# BartendingRobotPCB.net
KiCad netlist of a schematic drawn in EAGLE
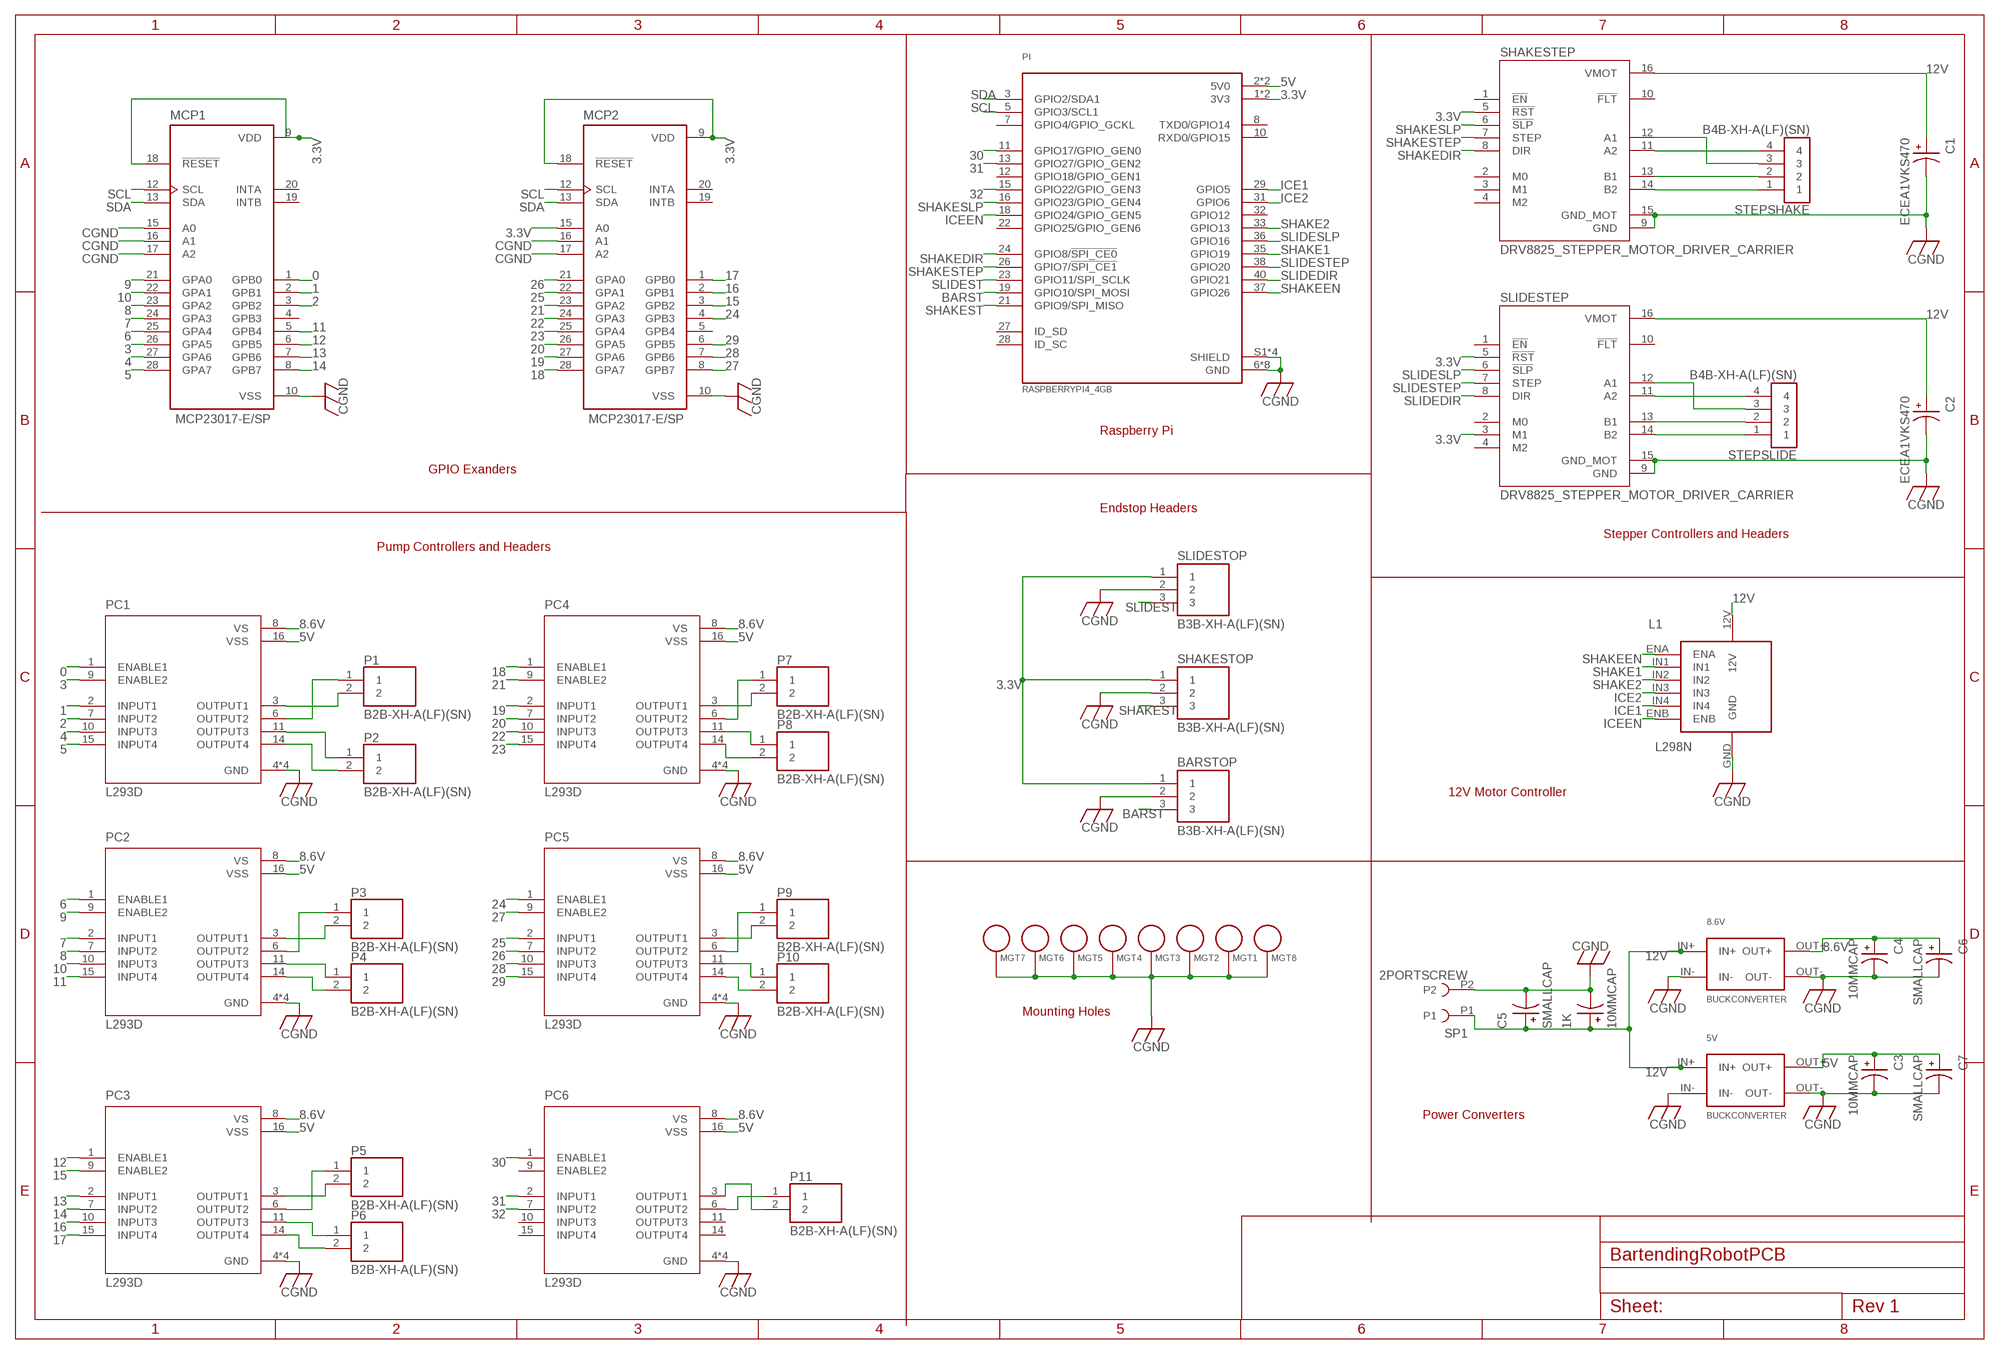
[diagram p0: schematic, sheet 1]

(export (version "E")
  (design (tool "Eeschema 10.0.6"))
  (components
    (comp (ref "1K")
      (value "10MMCAP")
      (footprint "eagle-import:10MMCAP")
      (libsource (lib "eagle-import") (part "10MMCAP"))
    )
    (comp (ref "5V")
      (value "BUCKCONVERTER")
      (footprint "eagle-import:BUCKCONVERTER")
      (libsource (lib "eagle-import") (part "BUCKCONVERTER"))
    )
    (comp (ref "8.6V")
      (value "BUCKCONVERTER")
      (footprint "eagle-import:BUCKCONVERTER")
      (libsource (lib "eagle-import") (part "BUCKCONVERTER"))
    )
    (comp (ref "BARSTOP")
      (value "B3B-XH-A(LF)(SN)")
      (footprint "eagle-import:JST_B3B-XH-A(LF)(SN)")
      (fields (field (name "MF") "JST Sales"))
      (libsource (lib "eagle-import") (part "B3B-XH-A(LF)(SN)"))
    )
    (comp (ref "C1")
      (value "ECEA1VKS470")
      (footprint "eagle-import:CAPPRD250W45D800H500")
      (fields (field (name "MF") "PANASONIC"))
      (libsource (lib "eagle-import") (part "ECEA1VKS470"))
    )
    (comp (ref "C2")
      (value "ECEA1VKS470")
      (footprint "eagle-import:CAPPRD250W45D800H500")
      (fields (field (name "MF") "PANASONIC"))
      (libsource (lib "eagle-import") (part "ECEA1VKS470"))
    )
    (comp (ref "C3")
      (value "10MMCAP")
      (footprint "eagle-import:10MMCAP")
      (libsource (lib "eagle-import") (part "10MMCAP"))
    )
    (comp (ref "C4")
      (value "10MMCAP")
      (footprint "eagle-import:10MMCAP")
      (libsource (lib "eagle-import") (part "10MMCAP"))
    )
    (comp (ref "C5")
      (value "SMALLCAP")
      (footprint "eagle-import:SMALLCAP")
      (libsource (lib "eagle-import") (part "SMALLCAP"))
    )
    (comp (ref "C6")
      (value "SMALLCAP")
      (footprint "eagle-import:SMALLCAP")
      (libsource (lib "eagle-import") (part "SMALLCAP"))
    )
    (comp (ref "C7")
      (value "SMALLCAP")
      (footprint "eagle-import:SMALLCAP")
      (libsource (lib "eagle-import") (part "SMALLCAP"))
    )
    (comp (ref "L1")
      (value "L298N")
      (footprint "eagle-import:L298N")
      (libsource (lib "eagle-import") (part "L298N"))
    )
    (comp (ref "MCP1")
      (value "MCP23017-E/SP")
      (footprint "eagle-import:DIP787W45P254L3556H508Q28")
      (fields (field (name "MF") "Microchip"))
      (libsource (lib "eagle-import") (part "MCP23017-E/SP"))
    )
    (comp (ref "MCP2")
      (value "MCP23017-E/SP")
      (footprint "eagle-import:DIP787W45P254L3556H508Q28")
      (fields (field (name "MF") "Microchip"))
      (libsource (lib "eagle-import") (part "MCP23017-E/SP"))
    )
    (comp (ref "MGT1")
      (value "MOUNTING_HOLE")
      (footprint "eagle-import:MOUNTING_HOLE")
      (libsource (lib "eagle-import") (part "MOUNTING_HOLE"))
    )
    (comp (ref "MGT2")
      (value "MOUNTING_HOLE")
      (footprint "eagle-import:MOUNTING_HOLE")
      (libsource (lib "eagle-import") (part "MOUNTING_HOLE"))
    )
    (comp (ref "MGT3")
      (value "MOUNTING_HOLE")
      (footprint "eagle-import:MOUNTING_HOLE")
      (libsource (lib "eagle-import") (part "MOUNTING_HOLE"))
    )
    (comp (ref "MGT4")
      (value "MOUNTING_HOLE")
      (footprint "eagle-import:MOUNTING_HOLE")
      (libsource (lib "eagle-import") (part "MOUNTING_HOLE"))
    )
    (comp (ref "MGT5")
      (value "MOUNTING_HOLE")
      (footprint "eagle-import:MOUNTING_HOLE")
      (libsource (lib "eagle-import") (part "MOUNTING_HOLE"))
    )
    (comp (ref "MGT6")
      (value "MOUNTING_HOLE")
      (footprint "eagle-import:MOUNTING_HOLE")
      (libsource (lib "eagle-import") (part "MOUNTING_HOLE"))
    )
    (comp (ref "MGT7")
      (value "MOUNTING_HOLE")
      (footprint "eagle-import:MOUNTING_HOLE")
      (libsource (lib "eagle-import") (part "MOUNTING_HOLE"))
    )
    (comp (ref "MGT8")
      (value "MOUNTING_HOLE")
      (footprint "eagle-import:MOUNTING_HOLE")
      (libsource (lib "eagle-import") (part "MOUNTING_HOLE"))
    )
    (comp (ref "P1")
      (value "B2B-XH-A(LF)(SN)")
      (footprint "eagle-import:JST_B2B-XH-A(LF)(SN)")
      (fields (field (name "MF") "JST Sales"))
      (libsource (lib "eagle-import") (part "B2B-XH-A(LF)(SN)"))
    )
    (comp (ref "P2")
      (value "B2B-XH-A(LF)(SN)")
      (footprint "eagle-import:JST_B2B-XH-A(LF)(SN)")
      (fields (field (name "MF") "JST Sales"))
      (libsource (lib "eagle-import") (part "B2B-XH-A(LF)(SN)"))
    )
    (comp (ref "P3")
      (value "B2B-XH-A(LF)(SN)")
      (footprint "eagle-import:JST_B2B-XH-A(LF)(SN)")
      (fields (field (name "MF") "JST Sales"))
      (libsource (lib "eagle-import") (part "B2B-XH-A(LF)(SN)"))
    )
    (comp (ref "P4")
      (value "B2B-XH-A(LF)(SN)")
      (footprint "eagle-import:JST_B2B-XH-A(LF)(SN)")
      (fields (field (name "MF") "JST Sales"))
      (libsource (lib "eagle-import") (part "B2B-XH-A(LF)(SN)"))
    )
    (comp (ref "P5")
      (value "B2B-XH-A(LF)(SN)")
      (footprint "eagle-import:JST_B2B-XH-A(LF)(SN)")
      (fields (field (name "MF") "JST Sales"))
      (libsource (lib "eagle-import") (part "B2B-XH-A(LF)(SN)"))
    )
    (comp (ref "P6")
      (value "B2B-XH-A(LF)(SN)")
      (footprint "eagle-import:JST_B2B-XH-A(LF)(SN)")
      (fields (field (name "MF") "JST Sales"))
      (libsource (lib "eagle-import") (part "B2B-XH-A(LF)(SN)"))
    )
    (comp (ref "P7")
      (value "B2B-XH-A(LF)(SN)")
      (footprint "eagle-import:JST_B2B-XH-A(LF)(SN)")
      (fields (field (name "MF") "JST Sales"))
      (libsource (lib "eagle-import") (part "B2B-XH-A(LF)(SN)"))
    )
    (comp (ref "P8")
      (value "B2B-XH-A(LF)(SN)")
      (footprint "eagle-import:JST_B2B-XH-A(LF)(SN)")
      (fields (field (name "MF") "JST Sales"))
      (libsource (lib "eagle-import") (part "B2B-XH-A(LF)(SN)"))
    )
    (comp (ref "P9")
      (value "B2B-XH-A(LF)(SN)")
      (footprint "eagle-import:JST_B2B-XH-A(LF)(SN)")
      (fields (field (name "MF") "JST Sales"))
      (libsource (lib "eagle-import") (part "B2B-XH-A(LF)(SN)"))
    )
    (comp (ref "P10")
      (value "B2B-XH-A(LF)(SN)")
      (footprint "eagle-import:JST_B2B-XH-A(LF)(SN)")
      (fields (field (name "MF") "JST Sales"))
      (libsource (lib "eagle-import") (part "B2B-XH-A(LF)(SN)"))
    )
    (comp (ref "P11")
      (value "B2B-XH-A(LF)(SN)")
      (footprint "eagle-import:JST_B2B-XH-A(LF)(SN)")
      (fields (field (name "MF") "JST Sales"))
      (libsource (lib "eagle-import") (part "B2B-XH-A(LF)(SN)"))
    )
    (comp (ref "PC1")
      (value "L293D")
      (footprint "eagle-import:DIP880W50P254L2000H510Q16")
      (fields (field (name "MANUFACTURER") "ST Microelectronics"))
      (libsource (lib "eagle-import") (part "L293D"))
    )
    (comp (ref "PC2")
      (value "L293D")
      (footprint "eagle-import:DIP880W50P254L2000H510Q16")
      (fields (field (name "MANUFACTURER") "ST Microelectronics"))
      (libsource (lib "eagle-import") (part "L293D"))
    )
    (comp (ref "PC3")
      (value "L293D")
      (footprint "eagle-import:DIP880W50P254L2000H510Q16")
      (fields (field (name "MANUFACTURER") "ST Microelectronics"))
      (libsource (lib "eagle-import") (part "L293D"))
    )
    (comp (ref "PC4")
      (value "L293D")
      (footprint "eagle-import:DIP880W50P254L2000H510Q16")
      (fields (field (name "MANUFACTURER") "ST Microelectronics"))
      (libsource (lib "eagle-import") (part "L293D"))
    )
    (comp (ref "PC5")
      (value "L293D")
      (footprint "eagle-import:DIP880W50P254L2000H510Q16")
      (fields (field (name "MANUFACTURER") "ST Microelectronics"))
      (libsource (lib "eagle-import") (part "L293D"))
    )
    (comp (ref "PC6")
      (value "L293D")
      (footprint "eagle-import:DIP880W50P254L2000H510Q16")
      (fields (field (name "MANUFACTURER") "ST Microelectronics"))
      (libsource (lib "eagle-import") (part "L293D"))
    )
    (comp (ref "PI")
      (value "RASPBERRYPI4_4GB")
      (footprint "eagle-import:MODULE_RASPBERRYPI4_4GB")
      (fields (field (name "MANUFACTURER") "Raspberry Pi"))
      (libsource (lib "eagle-import") (part "RASPBERRYPI4_4GB"))
    )
    (comp (ref "SHAKESTEP")
      (value "DRV8825_STEPPER_MOTOR_DRIVER_CARRIER")
      (footprint "eagle-import:IC_DRV8825_STEPPER_MOTOR_DRIVER_CARRIER")
      (fields (field (name "MF") "Pololu") (field (name "MP") "DRV8825 STEPPER MOTOR DRIVER CARRIER"))
      (libsource (lib "eagle-import") (part "DRV8825_STEPPER_MOTOR_DRIVER_CARRIER"))
    )
    (comp (ref "SHAKESTOP")
      (value "B3B-XH-A(LF)(SN)")
      (footprint "eagle-import:JST_B3B-XH-A(LF)(SN)")
      (fields (field (name "MF") "JST Sales"))
      (libsource (lib "eagle-import") (part "B3B-XH-A(LF)(SN)"))
    )
    (comp (ref "SLIDESTEP")
      (value "DRV8825_STEPPER_MOTOR_DRIVER_CARRIER")
      (footprint "eagle-import:IC_DRV8825_STEPPER_MOTOR_DRIVER_CARRIER")
      (fields (field (name "MF") "Pololu") (field (name "MP") "DRV8825 STEPPER MOTOR DRIVER CARRIER"))
      (libsource (lib "eagle-import") (part "DRV8825_STEPPER_MOTOR_DRIVER_CARRIER"))
    )
    (comp (ref "SLIDESTOP")
      (value "B3B-XH-A(LF)(SN)")
      (footprint "eagle-import:JST_B3B-XH-A(LF)(SN)")
      (fields (field (name "MF") "JST Sales"))
      (libsource (lib "eagle-import") (part "B3B-XH-A(LF)(SN)"))
    )
    (comp (ref "SP1")
      (value "2PORTSCREW")
      (footprint "eagle-import:2PORTSCREW")
      (libsource (lib "eagle-import") (part "2PORTSCREW"))
    )
    (comp (ref "STEPSHAKE")
      (value "B4B-XH-A(LF)(SN)")
      (footprint "eagle-import:JST_B4B-XH-A(LF)(SN)")
      (fields (field (name "MANUFACTURER") " JST Sales America Inc"))
      (libsource (lib "eagle-import") (part "B4B-XH-A(LF)(SN)"))
    )
    (comp (ref "STEPSLIDE")
      (value "B4B-XH-A(LF)(SN)")
      (footprint "eagle-import:JST_B4B-XH-A(LF)(SN)")
      (fields (field (name "MANUFACTURER") " JST Sales America Inc"))
      (libsource (lib "eagle-import") (part "B4B-XH-A(LF)(SN)"))
    )
  )
  (nets
    (net (code "1") (name "0") (class "Default")
      (node (ref "MCP1") (pin "1") (pinfunction "GPB0_1") (pintype "bidirectional"))
      (node (ref "PC1") (pin "1") (pinfunction "ENABLE1_1") (pintype "input"))
    )
    (net (code "2") (name "1") (class "Default")
      (node (ref "MCP1") (pin "2") (pinfunction "GPB1_2") (pintype "bidirectional"))
      (node (ref "PC1") (pin "2") (pinfunction "INPUT1_2") (pintype "input"))
    )
    (net (code "3") (name "2") (class "Default")
      (node (ref "MCP1") (pin "3") (pinfunction "GPB2_3") (pintype "bidirectional"))
      (node (ref "PC1") (pin "7") (pinfunction "INPUT2_7") (pintype "input"))
    )
    (net (code "4") (name "3") (class "Default")
      (node (ref "MCP1") (pin "26") (pinfunction "GPA5_26") (pintype "bidirectional"))
      (node (ref "PC1") (pin "9") (pinfunction "ENABLE2_9") (pintype "input"))
    )
    (net (code "5") (name "3.3V") (class "Default")
      (node (ref "BARSTOP") (pin "1") (pinfunction "1_1") (pintype "passive"))
      (node (ref "MCP1") (pin "18") (pinfunction "~{RESET}_18") (pintype "input"))
      (node (ref "MCP1") (pin "9") (pinfunction "VDD_9") (pintype "power_in"))
      (node (ref "MCP2") (pin "15") (pinfunction "A0_15") (pintype "input"))
      (node (ref "MCP2") (pin "18") (pinfunction "~{RESET}_18") (pintype "input"))
      (node (ref "MCP2") (pin "9") (pinfunction "VDD_9") (pintype "power_in"))
      (node (ref "PI") (pin "1") (pinfunction "3V3_1") (pintype "power_in"))
      (node (ref "PI") (pin "17") (pinfunction "3V3_17") (pintype "power_in"))
      (node (ref "SHAKESTEP") (pin "5") (pinfunction "~{RST}_5") (pintype "input"))
      (node (ref "SHAKESTOP") (pin "1") (pinfunction "1_1") (pintype "passive"))
      (node (ref "SLIDESTEP") (pin "3") (pinfunction "M1_3") (pintype "input"))
      (node (ref "SLIDESTEP") (pin "5") (pinfunction "~{RST}_5") (pintype "input"))
      (node (ref "SLIDESTOP") (pin "1") (pinfunction "1_1") (pintype "passive"))
    )
    (net (code "6") (name "4") (class "Default")
      (node (ref "MCP1") (pin "27") (pinfunction "GPA6_27") (pintype "bidirectional"))
      (node (ref "PC1") (pin "10") (pinfunction "INPUT3_10") (pintype "input"))
    )
    (net (code "7") (name "5") (class "Default")
      (node (ref "MCP1") (pin "28") (pinfunction "GPA7_28") (pintype "bidirectional"))
      (node (ref "PC1") (pin "15") (pinfunction "INPUT4_15") (pintype "input"))
    )
    (net (code "8") (name "5V") (class "Default")
      (node (ref "5V") (pin "OUT+") (pinfunction "OUT+_OUT+") (pintype "bidirectional"))
      (node (ref "C3") (pin "+") (pinfunction "P_+") (pintype "passive"))
      (node (ref "C7") (pin "+") (pinfunction "P_+") (pintype "passive"))
      (node (ref "PC1") (pin "16") (pinfunction "VSS_16") (pintype "power_in"))
      (node (ref "PC2") (pin "16") (pinfunction "VSS_16") (pintype "power_in"))
      (node (ref "PC3") (pin "16") (pinfunction "VSS_16") (pintype "power_in"))
      (node (ref "PC4") (pin "16") (pinfunction "VSS_16") (pintype "power_in"))
      (node (ref "PC5") (pin "16") (pinfunction "VSS_16") (pintype "power_in"))
      (node (ref "PC6") (pin "16") (pinfunction "VSS_16") (pintype "power_in"))
      (node (ref "PI") (pin "2") (pinfunction "5V0_2") (pintype "power_in"))
      (node (ref "PI") (pin "4") (pinfunction "5V0_4") (pintype "power_in"))
    )
    (net (code "9") (name "6") (class "Default")
      (node (ref "MCP1") (pin "25") (pinfunction "GPA4_25") (pintype "bidirectional"))
      (node (ref "PC2") (pin "1") (pinfunction "ENABLE1_1") (pintype "input"))
    )
    (net (code "10") (name "7") (class "Default")
      (node (ref "MCP1") (pin "24") (pinfunction "GPA3_24") (pintype "bidirectional"))
      (node (ref "PC2") (pin "2") (pinfunction "INPUT1_2") (pintype "input"))
    )
    (net (code "11") (name "8") (class "Default")
      (node (ref "MCP1") (pin "23") (pinfunction "GPA2_23") (pintype "bidirectional"))
      (node (ref "PC2") (pin "7") (pinfunction "INPUT2_7") (pintype "input"))
    )
    (net (code "12") (name "8.6V") (class "Default")
      (node (ref "8.6V") (pin "OUT+") (pinfunction "OUT+_OUT+") (pintype "bidirectional"))
      (node (ref "C4") (pin "+") (pinfunction "P_+") (pintype "passive"))
      (node (ref "C6") (pin "+") (pinfunction "P_+") (pintype "passive"))
      (node (ref "PC1") (pin "8") (pinfunction "VS_8") (pintype "power_in"))
      (node (ref "PC2") (pin "8") (pinfunction "VS_8") (pintype "power_in"))
      (node (ref "PC3") (pin "8") (pinfunction "VS_8") (pintype "power_in"))
      (node (ref "PC4") (pin "8") (pinfunction "VS_8") (pintype "power_in"))
      (node (ref "PC5") (pin "8") (pinfunction "VS_8") (pintype "power_in"))
      (node (ref "PC6") (pin "8") (pinfunction "VS_8") (pintype "power_in"))
    )
    (net (code "13") (name "9") (class "Default")
      (node (ref "MCP1") (pin "21") (pinfunction "GPA0_21") (pintype "bidirectional"))
      (node (ref "PC2") (pin "9") (pinfunction "ENABLE2_9") (pintype "input"))
    )
    (net (code "14") (name "10") (class "Default")
      (node (ref "MCP1") (pin "22") (pinfunction "GPA1_22") (pintype "bidirectional"))
      (node (ref "PC2") (pin "10") (pinfunction "INPUT3_10") (pintype "input"))
    )
    (net (code "15") (name "11") (class "Default")
      (node (ref "MCP1") (pin "5") (pinfunction "GPB4_5") (pintype "bidirectional"))
      (node (ref "PC2") (pin "15") (pinfunction "INPUT4_15") (pintype "input"))
    )
    (net (code "16") (name "12") (class "Default")
      (node (ref "MCP1") (pin "6") (pinfunction "GPB5_6") (pintype "bidirectional"))
      (node (ref "PC3") (pin "1") (pinfunction "ENABLE1_1") (pintype "input"))
    )
    (net (code "17") (name "12V") (class "Default")
      (node (ref "1K") (pin "+") (pinfunction "P_+") (pintype "passive"))
      (node (ref "5V") (pin "IN+") (pinfunction "IN+_IN+") (pintype "bidirectional"))
      (node (ref "8.6V") (pin "IN+") (pinfunction "IN+_IN+") (pintype "bidirectional"))
      (node (ref "C1") (pin "P") (pinfunction "P_P") (pintype "passive"))
      (node (ref "C2") (pin "P") (pinfunction "P_P") (pintype "passive"))
      (node (ref "C5") (pin "+") (pinfunction "P_+") (pintype "passive"))
      (node (ref "L1") (pin "12V") (pinfunction "12V_12V") (pintype "bidirectional"))
      (node (ref "SHAKESTEP") (pin "16") (pinfunction "VMOT_16") (pintype "power_in"))
      (node (ref "SLIDESTEP") (pin "16") (pinfunction "VMOT_16") (pintype "power_in"))
      (node (ref "SP1") (pin "P1") (pinfunction "P1_P1") (pintype "bidirectional"))
    )
    (net (code "18") (name "13") (class "Default")
      (node (ref "MCP1") (pin "7") (pinfunction "GPB6_7") (pintype "bidirectional"))
      (node (ref "PC3") (pin "2") (pinfunction "INPUT1_2") (pintype "input"))
    )
    (net (code "19") (name "14") (class "Default")
      (node (ref "MCP1") (pin "8") (pinfunction "GPB7_8") (pintype "bidirectional"))
      (node (ref "PC3") (pin "7") (pinfunction "INPUT2_7") (pintype "input"))
    )
    (net (code "20") (name "15") (class "Default")
      (node (ref "MCP2") (pin "3") (pinfunction "GPB2_3") (pintype "bidirectional"))
      (node (ref "PC3") (pin "9") (pinfunction "ENABLE2_9") (pintype "input"))
    )
    (net (code "21") (name "16") (class "Default")
      (node (ref "MCP2") (pin "2") (pinfunction "GPB1_2") (pintype "bidirectional"))
      (node (ref "PC3") (pin "10") (pinfunction "INPUT3_10") (pintype "input"))
    )
    (net (code "22") (name "17") (class "Default")
      (node (ref "MCP2") (pin "1") (pinfunction "GPB0_1") (pintype "bidirectional"))
      (node (ref "PC3") (pin "15") (pinfunction "INPUT4_15") (pintype "input"))
    )
    (net (code "23") (name "18") (class "Default")
      (node (ref "MCP2") (pin "28") (pinfunction "GPA7_28") (pintype "bidirectional"))
      (node (ref "PC4") (pin "1") (pinfunction "ENABLE1_1") (pintype "input"))
    )
    (net (code "24") (name "19") (class "Default")
      (node (ref "MCP2") (pin "27") (pinfunction "GPA6_27") (pintype "bidirectional"))
      (node (ref "PC4") (pin "2") (pinfunction "INPUT1_2") (pintype "input"))
    )
    (net (code "25") (name "20") (class "Default")
      (node (ref "MCP2") (pin "26") (pinfunction "GPA5_26") (pintype "bidirectional"))
      (node (ref "PC4") (pin "7") (pinfunction "INPUT2_7") (pintype "input"))
    )
    (net (code "26") (name "21") (class "Default")
      (node (ref "MCP2") (pin "23") (pinfunction "GPA2_23") (pintype "bidirectional"))
      (node (ref "PC4") (pin "9") (pinfunction "ENABLE2_9") (pintype "input"))
    )
    (net (code "27") (name "22") (class "Default")
      (node (ref "MCP2") (pin "24") (pinfunction "GPA3_24") (pintype "bidirectional"))
      (node (ref "PC4") (pin "10") (pinfunction "INPUT3_10") (pintype "input"))
    )
    (net (code "28") (name "23") (class "Default")
      (node (ref "MCP2") (pin "25") (pinfunction "GPA4_25") (pintype "bidirectional"))
      (node (ref "PC4") (pin "15") (pinfunction "INPUT4_15") (pintype "input"))
    )
    (net (code "29") (name "24") (class "Default")
      (node (ref "MCP2") (pin "4") (pinfunction "GPB3_4") (pintype "bidirectional"))
      (node (ref "PC5") (pin "1") (pinfunction "ENABLE1_1") (pintype "input"))
    )
    (net (code "30") (name "25") (class "Default")
      (node (ref "MCP2") (pin "22") (pinfunction "GPA1_22") (pintype "bidirectional"))
      (node (ref "PC5") (pin "2") (pinfunction "INPUT1_2") (pintype "input"))
    )
    (net (code "31") (name "26") (class "Default")
      (node (ref "MCP2") (pin "21") (pinfunction "GPA0_21") (pintype "bidirectional"))
      (node (ref "PC5") (pin "7") (pinfunction "INPUT2_7") (pintype "input"))
    )
    (net (code "32") (name "27") (class "Default")
      (node (ref "MCP2") (pin "8") (pinfunction "GPB7_8") (pintype "bidirectional"))
      (node (ref "PC5") (pin "9") (pinfunction "ENABLE2_9") (pintype "input"))
    )
    (net (code "33") (name "28") (class "Default")
      (node (ref "MCP2") (pin "7") (pinfunction "GPB6_7") (pintype "bidirectional"))
      (node (ref "PC5") (pin "10") (pinfunction "INPUT3_10") (pintype "input"))
    )
    (net (code "34") (name "29") (class "Default")
      (node (ref "MCP2") (pin "6") (pinfunction "GPB5_6") (pintype "bidirectional"))
      (node (ref "PC5") (pin "15") (pinfunction "INPUT4_15") (pintype "input"))
    )
    (net (code "35") (name "30") (class "Default")
      (node (ref "PC6") (pin "1") (pinfunction "ENABLE1_1") (pintype "input"))
      (node (ref "PI") (pin "11") (pinfunction "GPIO17/GPIO_GEN0_11") (pintype "bidirectional"))
    )
    (net (code "36") (name "31") (class "Default")
      (node (ref "PC6") (pin "2") (pinfunction "INPUT1_2") (pintype "input"))
      (node (ref "PI") (pin "13") (pinfunction "GPIO27/GPIO_GEN2_13") (pintype "bidirectional"))
    )
    (net (code "37") (name "32") (class "Default")
      (node (ref "PC6") (pin "7") (pinfunction "INPUT2_7") (pintype "input"))
      (node (ref "PI") (pin "15") (pinfunction "GPIO22/GPIO_GEN3_15") (pintype "bidirectional"))
    )
    (net (code "38") (name "BARST") (class "Default")
      (node (ref "BARSTOP") (pin "3") (pinfunction "3_3") (pintype "passive"))
      (node (ref "PI") (pin "19") (pinfunction "GPIO10/SPI_MOSI_19") (pintype "bidirectional"))
    )
    (net (code "39") (name "CGND") (class "Default")
      (node (ref "1K") (pin "-") (pinfunction "N_-") (pintype "passive"))
      (node (ref "5V") (pin "IN-") (pinfunction "IN-_IN-") (pintype "bidirectional"))
      (node (ref "5V") (pin "OUT-") (pinfunction "OUT-_OUT-") (pintype "bidirectional"))
      (node (ref "8.6V") (pin "IN-") (pinfunction "IN-_IN-") (pintype "bidirectional"))
      (node (ref "8.6V") (pin "OUT-") (pinfunction "OUT-_OUT-") (pintype "bidirectional"))
      (node (ref "BARSTOP") (pin "2") (pinfunction "2_2") (pintype "passive"))
      (node (ref "C1") (pin "N") (pinfunction "N_N") (pintype "passive"))
      (node (ref "C2") (pin "N") (pinfunction "N_N") (pintype "passive"))
      (node (ref "C3") (pin "-") (pinfunction "N_-") (pintype "passive"))
      (node (ref "C4") (pin "-") (pinfunction "N_-") (pintype "passive"))
      (node (ref "C5") (pin "-") (pinfunction "N_-") (pintype "passive"))
      (node (ref "C6") (pin "-") (pinfunction "N_-") (pintype "passive"))
      (node (ref "C7") (pin "-") (pinfunction "N_-") (pintype "passive"))
      (node (ref "L1") (pin "GND") (pinfunction "GND_GND") (pintype "bidirectional"))
      (node (ref "MCP1") (pin "10") (pinfunction "VSS_10") (pintype "power_in"))
      (node (ref "MCP1") (pin "15") (pinfunction "A0_15") (pintype "input"))
      (node (ref "MCP1") (pin "16") (pinfunction "A1_16") (pintype "input"))
      (node (ref "MCP1") (pin "17") (pinfunction "A2_17") (pintype "input"))
      (node (ref "MCP2") (pin "10") (pinfunction "VSS_10") (pintype "power_in"))
      (node (ref "MCP2") (pin "16") (pinfunction "A1_16") (pintype "input"))
      (node (ref "MCP2") (pin "17") (pinfunction "A2_17") (pintype "input"))
      (node (ref "MGT1") (pin "P$1") (pinfunction "P$1_P$1") (pintype "bidirectional"))
      (node (ref "MGT2") (pin "P$1") (pinfunction "P$1_P$1") (pintype "bidirectional"))
      (node (ref "MGT3") (pin "P$1") (pinfunction "P$1_P$1") (pintype "bidirectional"))
      (node (ref "MGT4") (pin "P$1") (pinfunction "P$1_P$1") (pintype "bidirectional"))
      (node (ref "MGT5") (pin "P$1") (pinfunction "P$1_P$1") (pintype "bidirectional"))
      (node (ref "MGT6") (pin "P$1") (pinfunction "P$1_P$1") (pintype "bidirectional"))
      (node (ref "MGT7") (pin "P$1") (pinfunction "P$1_P$1") (pintype "bidirectional"))
      (node (ref "MGT8") (pin "P$1") (pinfunction "P$1_P$1") (pintype "bidirectional"))
      (node (ref "PC1") (pin "12") (pinfunction "GND_12") (pintype "power_in"))
      (node (ref "PC1") (pin "13") (pinfunction "GND_13") (pintype "power_in"))
      (node (ref "PC1") (pin "4") (pinfunction "GND_4") (pintype "power_in"))
      (node (ref "PC1") (pin "5") (pinfunction "GND_5") (pintype "power_in"))
      (node (ref "PC2") (pin "12") (pinfunction "GND_12") (pintype "power_in"))
      (node (ref "PC2") (pin "13") (pinfunction "GND_13") (pintype "power_in"))
      (node (ref "PC2") (pin "4") (pinfunction "GND_4") (pintype "power_in"))
      (node (ref "PC2") (pin "5") (pinfunction "GND_5") (pintype "power_in"))
      (node (ref "PC3") (pin "12") (pinfunction "GND_12") (pintype "power_in"))
      (node (ref "PC3") (pin "13") (pinfunction "GND_13") (pintype "power_in"))
      (node (ref "PC3") (pin "4") (pinfunction "GND_4") (pintype "power_in"))
      (node (ref "PC3") (pin "5") (pinfunction "GND_5") (pintype "power_in"))
      (node (ref "PC4") (pin "12") (pinfunction "GND_12") (pintype "power_in"))
      (node (ref "PC4") (pin "13") (pinfunction "GND_13") (pintype "power_in"))
      (node (ref "PC4") (pin "4") (pinfunction "GND_4") (pintype "power_in"))
      (node (ref "PC4") (pin "5") (pinfunction "GND_5") (pintype "power_in"))
      (node (ref "PC5") (pin "12") (pinfunction "GND_12") (pintype "power_in"))
      (node (ref "PC5") (pin "13") (pinfunction "GND_13") (pintype "power_in"))
      (node (ref "PC5") (pin "4") (pinfunction "GND_4") (pintype "power_in"))
      (node (ref "PC5") (pin "5") (pinfunction "GND_5") (pintype "power_in"))
      (node (ref "PC6") (pin "12") (pinfunction "GND_12") (pintype "power_in"))
      (node (ref "PC6") (pin "13") (pinfunction "GND_13") (pintype "power_in"))
      (node (ref "PC6") (pin "4") (pinfunction "GND_4") (pintype "power_in"))
      (node (ref "PC6") (pin "5") (pinfunction "GND_5") (pintype "power_in"))
      (node (ref "PI") (pin "14") (pinfunction "GND_14") (pintype "power_in"))
      (node (ref "PI") (pin "20") (pinfunction "GND_20") (pintype "power_in"))
      (node (ref "PI") (pin "25") (pinfunction "GND_25") (pintype "power_in"))
      (node (ref "PI") (pin "30") (pinfunction "GND_30") (pintype "power_in"))
      (node (ref "PI") (pin "34") (pinfunction "GND_34") (pintype "power_in"))
      (node (ref "PI") (pin "39") (pinfunction "GND_39") (pintype "power_in"))
      (node (ref "PI") (pin "6") (pinfunction "GND_6") (pintype "power_in"))
      (node (ref "PI") (pin "9") (pinfunction "GND_9") (pintype "power_in"))
      (node (ref "PI") (pin "S1") (pinfunction "SHIELD_S1") (pintype "power_in"))
      (node (ref "PI") (pin "S2") (pinfunction "SHIELD_S2") (pintype "power_in"))
      (node (ref "PI") (pin "S3") (pinfunction "SHIELD_S3") (pintype "power_in"))
      (node (ref "PI") (pin "S4") (pinfunction "SHIELD_S4") (pintype "power_in"))
      (node (ref "SHAKESTEP") (pin "15") (pinfunction "GND_MOT_15") (pintype "power_in"))
      (node (ref "SHAKESTEP") (pin "9") (pinfunction "GND_9") (pintype "power_in"))
      (node (ref "SHAKESTOP") (pin "2") (pinfunction "2_2") (pintype "passive"))
      (node (ref "SLIDESTEP") (pin "15") (pinfunction "GND_MOT_15") (pintype "power_in"))
      (node (ref "SLIDESTEP") (pin "9") (pinfunction "GND_9") (pintype "power_in"))
      (node (ref "SLIDESTOP") (pin "2") (pinfunction "2_2") (pintype "passive"))
      (node (ref "SP1") (pin "P2") (pinfunction "P2_P2") (pintype "bidirectional"))
    )
    (net (code "40") (name "ICE1") (class "Default")
      (node (ref "L1") (pin "IN4") (pinfunction "IN4_IN4") (pintype "bidirectional"))
      (node (ref "PI") (pin "29") (pinfunction "GPIO5_29") (pintype "bidirectional"))
    )
    (net (code "41") (name "ICE2") (class "Default")
      (node (ref "L1") (pin "IN3") (pinfunction "IN3_IN3") (pintype "bidirectional"))
      (node (ref "PI") (pin "31") (pinfunction "GPIO6_31") (pintype "bidirectional"))
    )
    (net (code "42") (name "ICEEN") (class "Default")
      (node (ref "L1") (pin "ENB") (pinfunction "ENB_ENB") (pintype "bidirectional"))
      (node (ref "PI") (pin "18") (pinfunction "GPIO24/GPIO_GEN5_18") (pintype "bidirectional"))
    )
    (net (code "43") (name "Net-(PC1-OUTPUT1)") (class "Default")
      (node (ref "P1") (pin "2") (pinfunction "2_2") (pintype "passive"))
      (node (ref "PC1") (pin "3") (pinfunction "OUTPUT1_3") (pintype "output"))
    )
    (net (code "44") (name "Net-(PC1-OUTPUT2)") (class "Default")
      (node (ref "P1") (pin "1") (pinfunction "1_1") (pintype "passive"))
      (node (ref "PC1") (pin "6") (pinfunction "OUTPUT2_6") (pintype "output"))
    )
    (net (code "45") (name "Net-(PC1-OUTPUT3)") (class "Default")
      (node (ref "P2") (pin "1") (pinfunction "1_1") (pintype "passive"))
      (node (ref "PC1") (pin "11") (pinfunction "OUTPUT3_11") (pintype "output"))
    )
    (net (code "46") (name "Net-(PC1-OUTPUT4)") (class "Default")
      (node (ref "P2") (pin "2") (pinfunction "2_2") (pintype "passive"))
      (node (ref "PC1") (pin "14") (pinfunction "OUTPUT4_14") (pintype "output"))
    )
    (net (code "47") (name "Net-(PC2-OUTPUT1)") (class "Default")
      (node (ref "P3") (pin "2") (pinfunction "2_2") (pintype "passive"))
      (node (ref "PC2") (pin "3") (pinfunction "OUTPUT1_3") (pintype "output"))
    )
    (net (code "48") (name "Net-(PC2-OUTPUT2)") (class "Default")
      (node (ref "P3") (pin "1") (pinfunction "1_1") (pintype "passive"))
      (node (ref "PC2") (pin "6") (pinfunction "OUTPUT2_6") (pintype "output"))
    )
    (net (code "49") (name "Net-(PC2-OUTPUT3)") (class "Default")
      (node (ref "P4") (pin "1") (pinfunction "1_1") (pintype "passive"))
      (node (ref "PC2") (pin "11") (pinfunction "OUTPUT3_11") (pintype "output"))
    )
    (net (code "50") (name "Net-(PC2-OUTPUT4)") (class "Default")
      (node (ref "P4") (pin "2") (pinfunction "2_2") (pintype "passive"))
      (node (ref "PC2") (pin "14") (pinfunction "OUTPUT4_14") (pintype "output"))
    )
    (net (code "51") (name "Net-(PC3-OUTPUT1)") (class "Default")
      (node (ref "P5") (pin "2") (pinfunction "2_2") (pintype "passive"))
      (node (ref "PC3") (pin "3") (pinfunction "OUTPUT1_3") (pintype "output"))
    )
    (net (code "52") (name "Net-(PC3-OUTPUT2)") (class "Default")
      (node (ref "P5") (pin "1") (pinfunction "1_1") (pintype "passive"))
      (node (ref "PC3") (pin "6") (pinfunction "OUTPUT2_6") (pintype "output"))
    )
    (net (code "53") (name "Net-(PC3-OUTPUT3)") (class "Default")
      (node (ref "P6") (pin "1") (pinfunction "1_1") (pintype "passive"))
      (node (ref "PC3") (pin "11") (pinfunction "OUTPUT3_11") (pintype "output"))
    )
    (net (code "54") (name "Net-(PC3-OUTPUT4)") (class "Default")
      (node (ref "P6") (pin "2") (pinfunction "2_2") (pintype "passive"))
      (node (ref "PC3") (pin "14") (pinfunction "OUTPUT4_14") (pintype "output"))
    )
    (net (code "55") (name "Net-(PC4-OUTPUT1)") (class "Default")
      (node (ref "P7") (pin "2") (pinfunction "2_2") (pintype "passive"))
      (node (ref "PC4") (pin "3") (pinfunction "OUTPUT1_3") (pintype "output"))
    )
    (net (code "56") (name "Net-(PC4-OUTPUT2)") (class "Default")
      (node (ref "P7") (pin "1") (pinfunction "1_1") (pintype "passive"))
      (node (ref "PC4") (pin "6") (pinfunction "OUTPUT2_6") (pintype "output"))
    )
    (net (code "57") (name "Net-(PC4-OUTPUT3)") (class "Default")
      (node (ref "P8") (pin "1") (pinfunction "1_1") (pintype "passive"))
      (node (ref "PC4") (pin "11") (pinfunction "OUTPUT3_11") (pintype "output"))
    )
    (net (code "58") (name "Net-(PC4-OUTPUT4)") (class "Default")
      (node (ref "P8") (pin "2") (pinfunction "2_2") (pintype "passive"))
      (node (ref "PC4") (pin "14") (pinfunction "OUTPUT4_14") (pintype "output"))
    )
    (net (code "59") (name "Net-(PC5-OUTPUT1)") (class "Default")
      (node (ref "P9") (pin "2") (pinfunction "2_2") (pintype "passive"))
      (node (ref "PC5") (pin "3") (pinfunction "OUTPUT1_3") (pintype "output"))
    )
    (net (code "60") (name "Net-(PC5-OUTPUT2)") (class "Default")
      (node (ref "P9") (pin "1") (pinfunction "1_1") (pintype "passive"))
      (node (ref "PC5") (pin "6") (pinfunction "OUTPUT2_6") (pintype "output"))
    )
    (net (code "61") (name "Net-(PC5-OUTPUT3)") (class "Default")
      (node (ref "P10") (pin "1") (pinfunction "1_1") (pintype "passive"))
      (node (ref "PC5") (pin "11") (pinfunction "OUTPUT3_11") (pintype "output"))
    )
    (net (code "62") (name "Net-(PC5-OUTPUT4)") (class "Default")
      (node (ref "P10") (pin "2") (pinfunction "2_2") (pintype "passive"))
      (node (ref "PC5") (pin "14") (pinfunction "OUTPUT4_14") (pintype "output"))
    )
    (net (code "63") (name "Net-(PC6-OUTPUT1)") (class "Default")
      (node (ref "P11") (pin "2") (pinfunction "2_2") (pintype "passive"))
      (node (ref "PC6") (pin "3") (pinfunction "OUTPUT1_3") (pintype "output"))
    )
    (net (code "64") (name "Net-(PC6-OUTPUT2)") (class "Default")
      (node (ref "P11") (pin "1") (pinfunction "1_1") (pintype "passive"))
      (node (ref "PC6") (pin "6") (pinfunction "OUTPUT2_6") (pintype "output"))
    )
    (net (code "65") (name "Net-(SHAKESTEP-A1)") (class "Default")
      (node (ref "SHAKESTEP") (pin "12") (pinfunction "A1_12") (pintype "output"))
      (node (ref "STEPSHAKE") (pin "3") (pinfunction "3_3") (pintype "passive"))
    )
    (net (code "66") (name "Net-(SHAKESTEP-A2)") (class "Default")
      (node (ref "SHAKESTEP") (pin "11") (pinfunction "A2_11") (pintype "output"))
      (node (ref "STEPSHAKE") (pin "4") (pinfunction "4_4") (pintype "passive"))
    )
    (net (code "67") (name "Net-(SHAKESTEP-B1)") (class "Default")
      (node (ref "SHAKESTEP") (pin "13") (pinfunction "B1_13") (pintype "output"))
      (node (ref "STEPSHAKE") (pin "2") (pinfunction "2_2") (pintype "passive"))
    )
    (net (code "68") (name "Net-(SHAKESTEP-B2)") (class "Default")
      (node (ref "SHAKESTEP") (pin "14") (pinfunction "B2_14") (pintype "output"))
      (node (ref "STEPSHAKE") (pin "1") (pinfunction "1_1") (pintype "passive"))
    )
    (net (code "69") (name "Net-(SLIDESTEP-A1)") (class "Default")
      (node (ref "SLIDESTEP") (pin "12") (pinfunction "A1_12") (pintype "output"))
      (node (ref "STEPSLIDE") (pin "3") (pinfunction "3_3") (pintype "passive"))
    )
    (net (code "70") (name "Net-(SLIDESTEP-A2)") (class "Default")
      (node (ref "SLIDESTEP") (pin "11") (pinfunction "A2_11") (pintype "output"))
      (node (ref "STEPSLIDE") (pin "4") (pinfunction "4_4") (pintype "passive"))
    )
    (net (code "71") (name "Net-(SLIDESTEP-B1)") (class "Default")
      (node (ref "SLIDESTEP") (pin "13") (pinfunction "B1_13") (pintype "output"))
      (node (ref "STEPSLIDE") (pin "2") (pinfunction "2_2") (pintype "passive"))
    )
    (net (code "72") (name "Net-(SLIDESTEP-B2)") (class "Default")
      (node (ref "SLIDESTEP") (pin "14") (pinfunction "B2_14") (pintype "output"))
      (node (ref "STEPSLIDE") (pin "1") (pinfunction "1_1") (pintype "passive"))
    )
    (net (code "73") (name "SCL") (class "Default")
      (node (ref "MCP1") (pin "12") (pinfunction "SCL_12") (pintype "input"))
      (node (ref "MCP2") (pin "12") (pinfunction "SCL_12") (pintype "input"))
      (node (ref "PI") (pin "5") (pinfunction "GPIO3/SCL1_5") (pintype "bidirectional"))
    )
    (net (code "74") (name "SDA") (class "Default")
      (node (ref "MCP1") (pin "13") (pinfunction "SDA_13") (pintype "bidirectional"))
      (node (ref "MCP2") (pin "13") (pinfunction "SDA_13") (pintype "bidirectional"))
      (node (ref "PI") (pin "3") (pinfunction "GPIO2/SDA1_3") (pintype "bidirectional"))
    )
    (net (code "75") (name "SHAKE1") (class "Default")
      (node (ref "L1") (pin "IN1") (pinfunction "IN1_IN1") (pintype "bidirectional"))
      (node (ref "PI") (pin "35") (pinfunction "GPIO19_35") (pintype "bidirectional"))
    )
    (net (code "76") (name "SHAKE2") (class "Default")
      (node (ref "L1") (pin "IN2") (pinfunction "IN2_IN2") (pintype "bidirectional"))
      (node (ref "PI") (pin "33") (pinfunction "GPIO13_33") (pintype "bidirectional"))
    )
    (net (code "77") (name "SHAKEDIR") (class "Default")
      (node (ref "PI") (pin "24") (pinfunction "GPIO8/~{SPI_CE0}_24") (pintype "bidirectional"))
      (node (ref "SHAKESTEP") (pin "8") (pinfunction "DIR_8") (pintype "input"))
    )
    (net (code "78") (name "SHAKEEN") (class "Default")
      (node (ref "L1") (pin "ENA") (pinfunction "ENA_ENA") (pintype "bidirectional"))
      (node (ref "PI") (pin "37") (pinfunction "GPIO26_37") (pintype "bidirectional"))
    )
    (net (code "79") (name "SHAKESLP") (class "Default")
      (node (ref "PI") (pin "16") (pinfunction "GPIO23/GPIO_GEN4_16") (pintype "bidirectional"))
      (node (ref "SHAKESTEP") (pin "6") (pinfunction "~{SLP}_6") (pintype "input"))
    )
    (net (code "80") (name "SHAKEST") (class "Default")
      (node (ref "PI") (pin "21") (pinfunction "GPIO9/SPI_MISO_21") (pintype "bidirectional"))
      (node (ref "SHAKESTOP") (pin "3") (pinfunction "3_3") (pintype "passive"))
    )
    (net (code "81") (name "SHAKESTEP") (class "Default")
      (node (ref "PI") (pin "26") (pinfunction "GPIO7/~{SPI_CE1}_26") (pintype "bidirectional"))
      (node (ref "SHAKESTEP") (pin "7") (pinfunction "STEP_7") (pintype "input"))
    )
    (net (code "82") (name "SLIDEDIR") (class "Default")
      (node (ref "PI") (pin "40") (pinfunction "GPIO21_40") (pintype "bidirectional"))
      (node (ref "SLIDESTEP") (pin "8") (pinfunction "DIR_8") (pintype "input"))
    )
    (net (code "83") (name "SLIDESLP") (class "Default")
      (node (ref "PI") (pin "36") (pinfunction "GPIO16_36") (pintype "bidirectional"))
      (node (ref "SLIDESTEP") (pin "6") (pinfunction "~{SLP}_6") (pintype "input"))
    )
    (net (code "84") (name "SLIDEST") (class "Default")
      (node (ref "PI") (pin "23") (pinfunction "GPIO11/SPI_SCLK_23") (pintype "bidirectional"))
      (node (ref "SLIDESTOP") (pin "3") (pinfunction "3_3") (pintype "passive"))
    )
    (net (code "85") (name "SLIDESTEP") (class "Default")
      (node (ref "PI") (pin "38") (pinfunction "GPIO20_38") (pintype "bidirectional"))
      (node (ref "SLIDESTEP") (pin "7") (pinfunction "STEP_7") (pintype "input"))
    )
    (net (code "86") (name "unconnected-(MCP1-GPB3-Pad4)") (class "Default")
      (node (ref "MCP1") (pin "4") (pinfunction "GPB3_4") (pintype "bidirectional"))
    )
    (net (code "87") (name "unconnected-(MCP1-INTA-Pad20)") (class "Default")
      (node (ref "MCP1") (pin "20") (pinfunction "INTA_20") (pintype "output"))
    )
    (net (code "88") (name "unconnected-(MCP1-INTB-Pad19)") (class "Default")
      (node (ref "MCP1") (pin "19") (pinfunction "INTB_19") (pintype "output"))
    )
    (net (code "89") (name "unconnected-(MCP2-GPB4-Pad5)") (class "Default")
      (node (ref "MCP2") (pin "5") (pinfunction "GPB4_5") (pintype "bidirectional"))
    )
    (net (code "90") (name "unconnected-(MCP2-INTA-Pad20)") (class "Default")
      (node (ref "MCP2") (pin "20") (pinfunction "INTA_20") (pintype "output"))
    )
    (net (code "91") (name "unconnected-(MCP2-INTB-Pad19)") (class "Default")
      (node (ref "MCP2") (pin "19") (pinfunction "INTB_19") (pintype "output"))
    )
    (net (code "92") (name "unconnected-(PC6-ENABLE2-Pad9)") (class "Default")
      (node (ref "PC6") (pin "9") (pinfunction "ENABLE2_9") (pintype "input"))
    )
    (net (code "93") (name "unconnected-(PC6-INPUT3-Pad10)") (class "Default")
      (node (ref "PC6") (pin "10") (pinfunction "INPUT3_10") (pintype "input"))
    )
    (net (code "94") (name "unconnected-(PC6-INPUT4-Pad15)") (class "Default")
      (node (ref "PC6") (pin "15") (pinfunction "INPUT4_15") (pintype "input"))
    )
    (net (code "95") (name "unconnected-(PC6-OUTPUT3-Pad11)") (class "Default")
      (node (ref "PC6") (pin "11") (pinfunction "OUTPUT3_11") (pintype "output"))
    )
    (net (code "96") (name "unconnected-(PC6-OUTPUT4-Pad14)") (class "Default")
      (node (ref "PC6") (pin "14") (pinfunction "OUTPUT4_14") (pintype "output"))
    )
    (net (code "97") (name "unconnected-(PI-GPIO4{slash}GPIO_GCKL-Pad7)") (class "Default")
      (node (ref "PI") (pin "7") (pinfunction "GPIO4/GPIO_GCKL_7") (pintype "bidirectional"))
    )
    (net (code "98") (name "unconnected-(PI-GPIO12-Pad32)") (class "Default")
      (node (ref "PI") (pin "32") (pinfunction "GPIO12_32") (pintype "bidirectional"))
    )
    (net (code "99") (name "unconnected-(PI-GPIO18{slash}GPIO_GEN1-Pad12)") (class "Default")
      (node (ref "PI") (pin "12") (pinfunction "GPIO18/GPIO_GEN1_12") (pintype "bidirectional"))
    )
    (net (code "100") (name "unconnected-(PI-GPIO25{slash}GPIO_GEN6-Pad22)") (class "Default")
      (node (ref "PI") (pin "22") (pinfunction "GPIO25/GPIO_GEN6_22") (pintype "bidirectional"))
    )
    (net (code "101") (name "unconnected-(PI-ID_SC-Pad28)") (class "Default")
      (node (ref "PI") (pin "28") (pinfunction "ID_SC_28") (pintype "bidirectional"))
    )
    (net (code "102") (name "unconnected-(PI-ID_SD-Pad27)") (class "Default")
      (node (ref "PI") (pin "27") (pinfunction "ID_SD_27") (pintype "bidirectional"))
    )
    (net (code "103") (name "unconnected-(PI-RXD0{slash}GPIO15-Pad10)") (class "Default")
      (node (ref "PI") (pin "10") (pinfunction "RXD0/GPIO15_10") (pintype "bidirectional"))
    )
    (net (code "104") (name "unconnected-(PI-TXD0{slash}GPIO14-Pad8)") (class "Default")
      (node (ref "PI") (pin "8") (pinfunction "TXD0/GPIO14_8") (pintype "bidirectional"))
    )
    (net (code "105") (name "unconnected-(SHAKESTEP-M0-Pad2)") (class "Default")
      (node (ref "SHAKESTEP") (pin "2") (pinfunction "M0_2") (pintype "input"))
    )
    (net (code "106") (name "unconnected-(SHAKESTEP-M1-Pad3)") (class "Default")
      (node (ref "SHAKESTEP") (pin "3") (pinfunction "M1_3") (pintype "input"))
    )
    (net (code "107") (name "unconnected-(SHAKESTEP-M2-Pad4)") (class "Default")
      (node (ref "SHAKESTEP") (pin "4") (pinfunction "M2_4") (pintype "input"))
    )
    (net (code "108") (name "unconnected-(SHAKESTEP-~{EN}-Pad1)") (class "Default")
      (node (ref "SHAKESTEP") (pin "1") (pinfunction "~{EN}_1") (pintype "input"))
    )
    (net (code "109") (name "unconnected-(SHAKESTEP-~{FLT}-Pad10)") (class "Default")
      (node (ref "SHAKESTEP") (pin "10") (pinfunction "~{FLT}_10") (pintype "output"))
    )
    (net (code "110") (name "unconnected-(SLIDESTEP-M0-Pad2)") (class "Default")
      (node (ref "SLIDESTEP") (pin "2") (pinfunction "M0_2") (pintype "input"))
    )
    (net (code "111") (name "unconnected-(SLIDESTEP-M2-Pad4)") (class "Default")
      (node (ref "SLIDESTEP") (pin "4") (pinfunction "M2_4") (pintype "input"))
    )
    (net (code "112") (name "unconnected-(SLIDESTEP-~{EN}-Pad1)") (class "Default")
      (node (ref "SLIDESTEP") (pin "1") (pinfunction "~{EN}_1") (pintype "input"))
    )
    (net (code "113") (name "unconnected-(SLIDESTEP-~{FLT}-Pad10)") (class "Default")
      (node (ref "SLIDESTEP") (pin "10") (pinfunction "~{FLT}_10") (pintype "output"))
    )
  )
)
